# Main.net
KiCad netlist of a schematic drawn in Altium Designer
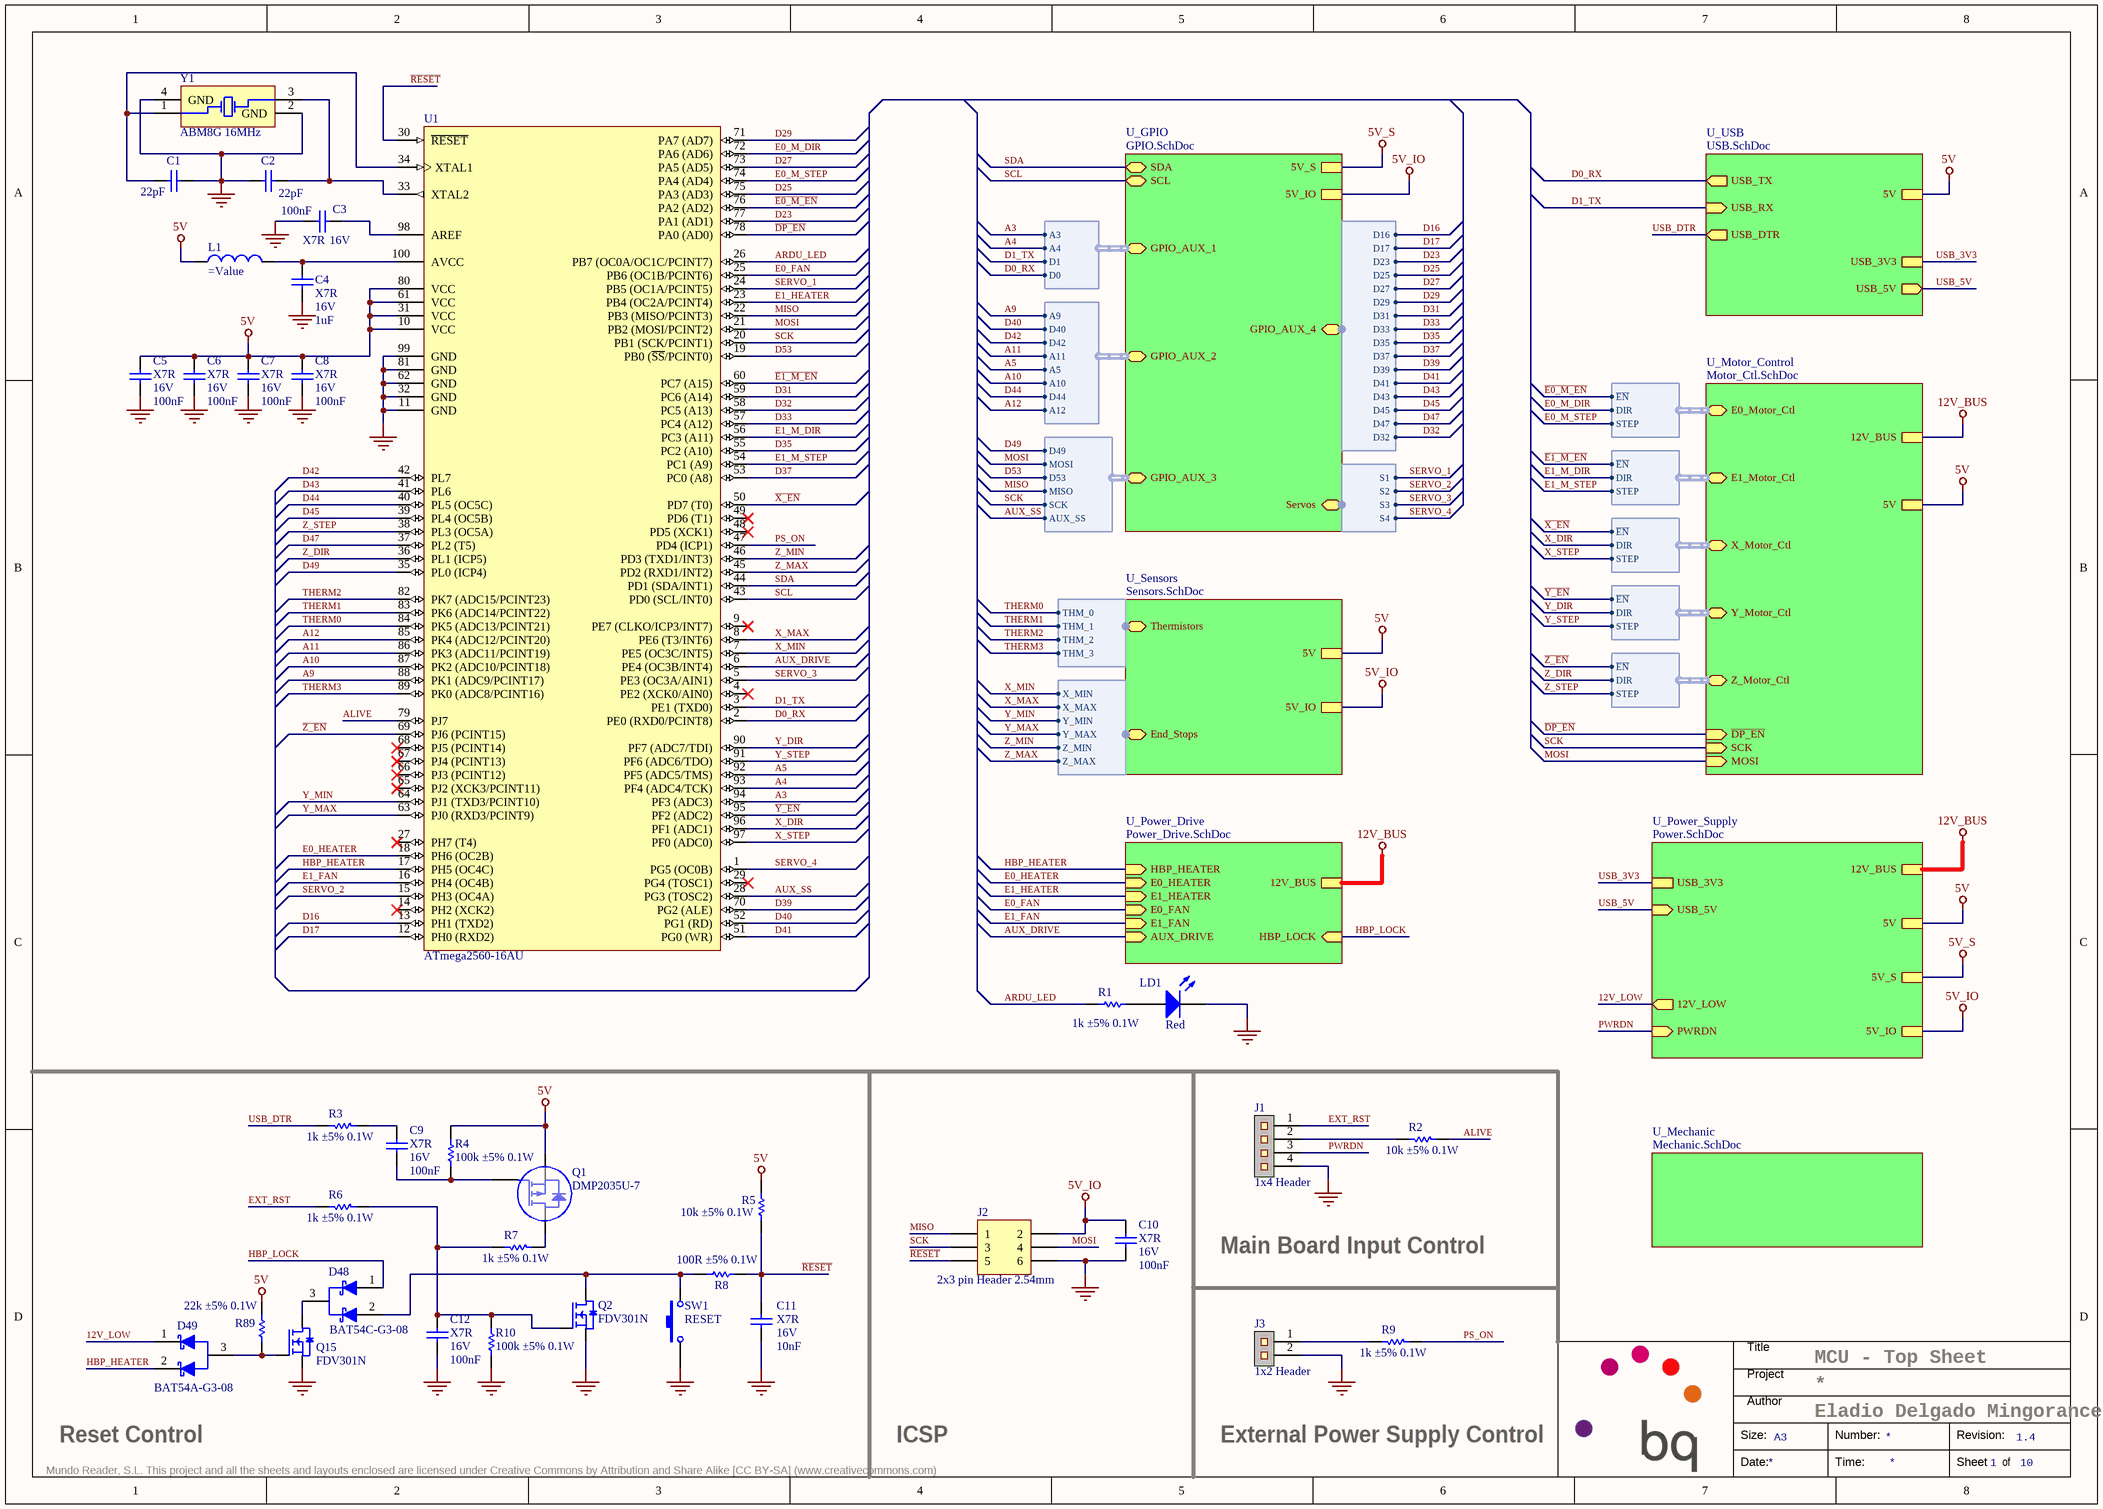
[diagram p0: Main.SchDoc]

(export (version "E")
  (design (tool "Eeschema 10.0.6"))
  (components
    (comp (ref "C1")
      (value "Capacitor")
      (footprint "C0603")
      (fields
        (field (name "VOLTAGE") "16V")
        (field (name "CAPACITANCE") "22pF")
        (field (name "PART NUMBER") "C0603_22pF_16V_±10%")
        (field (name "TOLERANCE") "±10%")
      )
      (libsource (lib "Pasives_Capacitor_SMD") (part "Capacitor"))
    )
    (comp (ref "C2")
      (value "Capacitor")
      (footprint "C0603")
      (fields
        (field (name "VOLTAGE") "16V")
        (field (name "CAPACITANCE") "22pF")
        (field (name "PART NUMBER") "C0603_22pF_16V_±10%")
        (field (name "TOLERANCE") "±10%")
      )
      (libsource (lib "Pasives_Capacitor_SMD") (part "Capacitor"))
    )
    (comp (ref "C3")
      (value "Capacitor")
      (footprint "C0603")
      (fields
        (field (name "DIELECTRIC") "X7R")
        (field (name "VOLTAGE") "16V")
        (field (name "CAPACITANCE") "100nF")
        (field (name "PART NUMBER") "C0603_100nF_16V_±10%")
        (field (name "TOLERANCE") "±10%")
        (field (name "MANUFACTURER") "Kemet")
      )
      (libsource (lib "Pasives_Capacitor_SMD") (part "Capacitor"))
    )
    (comp (ref "C4")
      (value "Capacitor")
      (footprint "C0603")
      (description "Capacitor SMD")
      (fields
        (field (name "DIELECTRIC") "X7R")
        (field (name "VOLTAGE") "16V")
        (field (name "CAPACITANCE") "1uF")
        (field (name "PART NUMBER") "C0603_1uF_16V_±10%_X7R")
        (field (name "TOLERANCE") "±10%")
      )
      (libsource (lib "Pasives_Capacitor_SMD") (part "Capacitor"))
    )
    (comp (ref "C5")
      (value "Capacitor")
      (footprint "C0603")
      (fields
        (field (name "DIELECTRIC") "X7R")
        (field (name "VOLTAGE") "16V")
        (field (name "CAPACITANCE") "100nF")
        (field (name "PART NUMBER") "C0603_100nF_16V_±10%")
        (field (name "TOLERANCE") "±10%")
        (field (name "MANUFACTURER") "Kemet")
      )
      (libsource (lib "Pasives_Capacitor_SMD") (part "Capacitor"))
    )
    (comp (ref "C6")
      (value "Capacitor")
      (footprint "C0603")
      (fields
        (field (name "DIELECTRIC") "X7R")
        (field (name "VOLTAGE") "16V")
        (field (name "CAPACITANCE") "100nF")
        (field (name "PART NUMBER") "C0603_100nF_16V_±10%")
        (field (name "TOLERANCE") "±10%")
        (field (name "MANUFACTURER") "Kemet")
      )
      (libsource (lib "Pasives_Capacitor_SMD") (part "Capacitor"))
    )
    (comp (ref "C7")
      (value "Capacitor")
      (footprint "C0603")
      (fields
        (field (name "DIELECTRIC") "X7R")
        (field (name "VOLTAGE") "16V")
        (field (name "CAPACITANCE") "100nF")
        (field (name "PART NUMBER") "C0603_100nF_16V_±10%")
        (field (name "TOLERANCE") "±10%")
        (field (name "MANUFACTURER") "Kemet")
      )
      (libsource (lib "Pasives_Capacitor_SMD") (part "Capacitor"))
    )
    (comp (ref "C8")
      (value "Capacitor")
      (footprint "C0603")
      (fields
        (field (name "DIELECTRIC") "X7R")
        (field (name "VOLTAGE") "16V")
        (field (name "CAPACITANCE") "100nF")
        (field (name "PART NUMBER") "C0603_100nF_16V_±10%")
        (field (name "TOLERANCE") "±10%")
        (field (name "MANUFACTURER") "Kemet")
      )
      (libsource (lib "Pasives_Capacitor_SMD") (part "Capacitor"))
    )
    (comp (ref "C9")
      (value "Capacitor")
      (footprint "C0603")
      (fields
        (field (name "DIELECTRIC") "X7R")
        (field (name "VOLTAGE") "16V")
        (field (name "CAPACITANCE") "100nF")
        (field (name "PART NUMBER") "C0603_100nF_16V_±10%")
        (field (name "TOLERANCE") "±10%")
        (field (name "MANUFACTURER") "Kemet")
      )
      (libsource (lib "Pasives_Capacitor_SMD") (part "Capacitor"))
    )
    (comp (ref "C10")
      (value "Capacitor")
      (footprint "C0603")
      (fields
        (field (name "DIELECTRIC") "X7R")
        (field (name "VOLTAGE") "16V")
        (field (name "CAPACITANCE") "100nF")
        (field (name "PART NUMBER") "C0603_100nF_16V_±10%")
        (field (name "TOLERANCE") "±10%")
        (field (name "MANUFACTURER") "Kemet")
      )
      (libsource (lib "Pasives_Capacitor_SMD") (part "Capacitor"))
    )
    (comp (ref "C11")
      (value "Capacitor")
      (footprint "C0603")
      (description "Capacitor SMD")
      (fields
        (field (name "DIELECTRIC") "X7R")
        (field (name "VOLTAGE") "16V")
        (field (name "CAPACITANCE") "10nF")
        (field (name "PART NUMBER") "C0603_10nF_16V_±10%")
        (field (name "TOLERANCE") "±10%")
      )
      (libsource (lib "Pasives_Capacitor_SMD") (part "Capacitor"))
    )
    (comp (ref "C12")
      (value "Capacitor")
      (footprint "C0603")
      (fields
        (field (name "DIELECTRIC") "X7R")
        (field (name "VOLTAGE") "16V")
        (field (name "CAPACITANCE") "100nF")
        (field (name "PART NUMBER") "C0603_100nF_16V_±10%")
        (field (name "TOLERANCE") "±10%")
        (field (name "MANUFACTURER") "Kemet")
      )
      (libsource (lib "Pasives_Capacitor_SMD") (part "Capacitor"))
    )
    (comp (ref "D48")
      (value "BAT54C-G3-08")
      (footprint "SOT23-3")
      (description "Dual Schottky Diode Common Cathode")
      (fields (field (name "PART NUMBER") "BAT54C") (field (name "MANUFACTURER") "Vishay"))
      (libsource (lib "Semiconductors_Diodes") (part "Dual_Diode_Schottky_BAT54C"))
    )
    (comp (ref "D49")
      (value "BAT54A-G3-08")
      (footprint "SOT23-3")
      (description "Dual Schottky Diode Common Anode")
      (fields (field (name "PART NUMBER") "BAT54A") (field (name "MANUFACTURER") "Vishay"))
      (libsource (lib "Semiconductors_Diodes") (part "Dual_Diode_Schottky_A"))
    )
    (comp (ref "J1")
      (value "1x4 Header")
      (footprint "1x4 MTE Straight Header 2.54mm")
      (description "1x4 MTE Straight Header 2.54mm")
      (fields
        (field (name "PART NUMBER") "CON_MTE_HDR_THT2.54_4")
        (field (name "MANUFACTURER") "TE Connectivity")
      )
      (libsource (lib "Conectores_MTE_Header_2.54") (part "1x4 MTE Straight Header 2.54mm"))
    )
    (comp (ref "J2")
      (value "2x3 pin Header 2.54mm")
      (footprint "2x3 Pin Header 2.54")
      (description "Connector, 6 pin Dual Header 2.54mm")
      (fields (field (name "MANUFACTURER") "Samtec") (field (name "PART NUMBER") "CON_DPH_THT2.54_6"))
      (libsource (lib "Conectores_PinHeader_2.54") (part "2x3 pin Header 2.54mm"))
    )
    (comp (ref "J3")
      (value "1x2 Header")
      (footprint "1x2 MTE Straight Header 2.54mm")
      (description "1x2 MTE Straight Header 2.54mm")
      (fields
        (field (name "PART NUMBER") "CON_MTE_HDR_THT2.54_2")
        (field (name "MANUFACTURER") "TE Connectivity")
      )
      (libsource (lib "Conectores_MTE_Header_2.54") (part "1x2 MTE Straight Header 2.54mm"))
    )
    (comp (ref "L1")
      (value "~")
      (footprint "L0805")
      (fields (field (name "PART NUMBER") "10uH_0,1A") (field (name "MANUFACTURER") "muRata"))
      (libsource (lib "Pasivos_Inductor_SMD") (part "Inductor"))
    )
    (comp (ref "LD1")
      (value "Red")
      (footprint "LED0603")
      (description "Light Emitting Diode")
      (fields (field (name "PART NUMBER") "HSMH-C190") (field (name "MANUFACTURER") "Avago Technologies"))
      (libsource (lib "Optoelectronics") (part "LED"))
    )
    (comp (ref "Q1")
      (value "DMP2035U-7")
      (footprint "SOT23-3")
      (description "Mosfet Channel P Enhancement Mode")
      (fields (field (name "PART NUMBER") "DMP2035U") (field (name "MANUFACTURER") "Diodes Incorporated"))
      (libsource (lib "Semiconductors_Transistors") (part "Mosfet_P"))
    )
    (comp (ref "Q2")
      (value "FDV301N")
      (footprint "SOT23-3")
      (description "Mosfet Channel N Enhancement Mode")
      (fields (field (name "MANUFACTURER") "Fairchild Semiconductor"))
      (libsource (lib "Semiconductors_Transistors") (part "Mosfet_N"))
    )
    (comp (ref "Q15")
      (value "FDV301N")
      (footprint "SOT23-3")
      (description "Mosfet Channel N Enhancement Mode")
      (fields (field (name "MANUFACTURER") "Fairchild Semiconductor"))
      (libsource (lib "Semiconductors_Transistors") (part "Mosfet_N"))
    )
    (comp (ref "R1")
      (value "1k ±5% 0.1W")
      (footprint "R0603")
      (description "Resistor")
      (fields (field (name "TOLERANCE") "±5%") (field (name "POWER") "0.1W"))
      (libsource (lib "Pasives_Resistor_SMD") (part "Resistor"))
    )
    (comp (ref "R2")
      (value "10k ±5% 0.1W")
      (footprint "R0603")
      (description "Resistor")
      (fields (field (name "TOLERANCE") "±5%") (field (name "POWER") "0.1W"))
      (libsource (lib "Pasives_Resistor_SMD") (part "Resistor"))
    )
    (comp (ref "R3")
      (value "1k ±5% 0.1W")
      (footprint "R0603")
      (description "Resistor")
      (fields (field (name "TOLERANCE") "±5%") (field (name "POWER") "0.1W"))
      (libsource (lib "Pasives_Resistor_SMD") (part "Resistor"))
    )
    (comp (ref "R4")
      (value "100k ±5% 0.1W")
      (footprint "R0603")
      (description "Resistor")
      (fields (field (name "TOLERANCE") "±5%") (field (name "POWER") "0.1W"))
      (libsource (lib "Pasives_Resistor_SMD") (part "Resistor"))
    )
    (comp (ref "R5")
      (value "10k ±5% 0.1W")
      (footprint "R0603")
      (description "Resistor")
      (fields (field (name "TOLERANCE") "±5%") (field (name "POWER") "0.1W"))
      (libsource (lib "Pasives_Resistor_SMD") (part "Resistor"))
    )
    (comp (ref "R6")
      (value "1k ±5% 0.1W")
      (footprint "R0603")
      (description "Resistor")
      (fields (field (name "TOLERANCE") "±5%") (field (name "POWER") "0.1W"))
      (libsource (lib "Pasives_Resistor_SMD") (part "Resistor"))
    )
    (comp (ref "R7")
      (value "1k ±5% 0.1W")
      (footprint "R0603")
      (description "Resistor")
      (fields (field (name "TOLERANCE") "±5%") (field (name "POWER") "0.1W"))
      (libsource (lib "Pasives_Resistor_SMD") (part "Resistor"))
    )
    (comp (ref "R8")
      (value "100R ±5% 0.1W")
      (footprint "R0603")
      (description "Resistor, SMD")
      (fields (field (name "TOLERANCE") "±5%") (field (name "POWER") "0.1W"))
      (libsource (lib "Pasives_Resistor_SMD") (part "Resistor"))
    )
    (comp (ref "R9")
      (value "1k ±5% 0.1W")
      (footprint "R0603")
      (description "Resistor")
      (fields (field (name "TOLERANCE") "±5%") (field (name "POWER") "0.1W"))
      (libsource (lib "Pasives_Resistor_SMD") (part "Resistor"))
    )
    (comp (ref "R10")
      (value "100k ±5% 0.1W")
      (footprint "R0603")
      (description "Resistor")
      (fields (field (name "TOLERANCE") "±5%") (field (name "POWER") "0.1W"))
      (libsource (lib "Pasives_Resistor_SMD") (part "Resistor"))
    )
    (comp (ref "R89")
      (value "22k ±5% 0.1W")
      (footprint "R0603")
      (description "Resistor, SMD")
      (fields (field (name "TOLERANCE") "±5%") (field (name "POWER") "0.1W"))
      (libsource (lib "Pasives_Resistor_SMD") (part "Resistor"))
    )
    (comp (ref "SW1")
      (value "RESET")
      (footprint "SW_Vert_THT_7.5x6x6.5")
      (description "Micro miniature pushbutton surface Switch")
      (fields (field (name "PART NUMBER") "SW Vertical THT") (field (name "MANUFACTURER") "C&K Components"))
      (libsource (lib "Electromechanical") (part "Switch"))
    )
    (comp (ref "U1")
      (value "ATmega2560-16AU")
      (footprint "TQFP100_05_MD")
      (fields (field (name "PART NUMBER") "Atmega2560") (field (name "MANUFACTURER") "Atmel"))
      (libsource (lib "Processor") (part "ATmega2560-16AU"))
    )
    (comp (ref "Y1")
      (value "ABM8G 16MHz")
      (footprint "ABM8G_3.2x2.5mm")
      (description "Crystal")
      (fields (field (name "TOLERANCE") "±20ppm") (field (name "MANUFACTURER") "Abracon"))
      (libsource (lib "Frequency") (part "Crystal 4 pin"))
    )
  )
  (nets
    (net (code "5") (name "/12V_LOW") (class "Default")
      (node (ref "D49") (pin "1") (pinfunction "A1_1") (pintype "passive"))
    )
    (net (code "6") (name "/A3") (class "Default")
      (node (ref "U1") (pin "94") (pinfunction "PF3_(ADC3)_94") (pintype "bidirectional"))
    )
    (net (code "7") (name "/A4") (class "Default")
      (node (ref "U1") (pin "93") (pinfunction "PF4_(ADC4/TCK)_93") (pintype "bidirectional"))
    )
    (net (code "8") (name "/A5") (class "Default")
      (node (ref "U1") (pin "92") (pinfunction "PF5_(ADC5/TMS)_92") (pintype "bidirectional"))
    )
    (net (code "9") (name "/A9") (class "Default")
      (node (ref "U1") (pin "88") (pinfunction "PK1_(ADC9/PCINT17)_88") (pintype "bidirectional"))
    )
    (net (code "10") (name "/A10") (class "Default")
      (node (ref "U1") (pin "87") (pinfunction "PK2_(ADC10/PCINT18)_87") (pintype "bidirectional"))
    )
    (net (code "11") (name "/A11") (class "Default")
      (node (ref "U1") (pin "86") (pinfunction "PK3_(ADC11/PCINT19)_86") (pintype "bidirectional"))
    )
    (net (code "12") (name "/A12") (class "Default")
      (node (ref "U1") (pin "85") (pinfunction "PK4_(ADC12/PCINT20)_85") (pintype "bidirectional"))
    )
    (net (code "13") (name "/ALIVE") (class "Default")
      (node (ref "R2") (pin "1") (pinfunction "1_1") (pintype "passive"))
      (node (ref "U1") (pin "79") (pinfunction "PJ7_79") (pintype "bidirectional"))
    )
    (net (code "14") (name "/ARDU_LED") (class "Default")
      (node (ref "R1") (pin "1") (pinfunction "1_1") (pintype "passive"))
      (node (ref "U1") (pin "26") (pinfunction "PB7_(OC0A/OC1C/PCINT7)_26") (pintype "bidirectional"))
    )
    (net (code "15") (name "/AUX_DRIVE") (class "Default")
      (node (ref "U1") (pin "6") (pinfunction "PE4_(OC3B/INT4)_6") (pintype "bidirectional"))
    )
    (net (code "16") (name "/AUX_SS") (class "Default")
      (node (ref "U1") (pin "28") (pinfunction "PG3_(TOSC2)_28") (pintype "bidirectional"))
    )
    (net (code "17") (name "/D0_RX") (class "Default")
      (node (ref "U1") (pin "2") (pinfunction "PE0_(RXD0/PCINT8)_2") (pintype "bidirectional"))
    )
    (net (code "18") (name "/D1_TX") (class "Default")
      (node (ref "U1") (pin "3") (pinfunction "PE1_(TXD0)_3") (pintype "bidirectional"))
    )
    (net (code "19") (name "/D16") (class "Default")
      (node (ref "U1") (pin "13") (pinfunction "PH1_(TXD2)_13") (pintype "bidirectional"))
    )
    (net (code "20") (name "/D17") (class "Default")
      (node (ref "U1") (pin "12") (pinfunction "PH0_(RXD2)_12") (pintype "bidirectional"))
    )
    (net (code "21") (name "/D23") (class "Default")
      (node (ref "U1") (pin "77") (pinfunction "PA1_(AD1)_77") (pintype "bidirectional"))
    )
    (net (code "22") (name "/D25") (class "Default")
      (node (ref "U1") (pin "75") (pinfunction "PA3_(AD3)_75") (pintype "bidirectional"))
    )
    (net (code "23") (name "/D27") (class "Default")
      (node (ref "U1") (pin "73") (pinfunction "PA5_(AD5)_73") (pintype "bidirectional"))
    )
    (net (code "24") (name "/D29") (class "Default")
      (node (ref "U1") (pin "71") (pinfunction "PA7_(AD7)_71") (pintype "bidirectional"))
    )
    (net (code "25") (name "/D31") (class "Default")
      (node (ref "U1") (pin "59") (pinfunction "PC6_(A14)_59") (pintype "bidirectional"))
    )
    (net (code "26") (name "/D32") (class "Default")
      (node (ref "U1") (pin "58") (pinfunction "PC5_(A13)_58") (pintype "bidirectional"))
    )
    (net (code "27") (name "/D33") (class "Default")
      (node (ref "U1") (pin "57") (pinfunction "PC4_(A12)_57") (pintype "bidirectional"))
    )
    (net (code "28") (name "/D35") (class "Default")
      (node (ref "U1") (pin "55") (pinfunction "PC2_(A10)_55") (pintype "bidirectional"))
    )
    (net (code "29") (name "/D37") (class "Default")
      (node (ref "U1") (pin "53") (pinfunction "PC0_(A8)_53") (pintype "bidirectional"))
    )
    (net (code "30") (name "/D39") (class "Default")
      (node (ref "U1") (pin "70") (pinfunction "PG2_(ALE)_70") (pintype "bidirectional"))
    )
    (net (code "31") (name "/D40") (class "Default")
      (node (ref "U1") (pin "52") (pinfunction "PG1_(RD)_52") (pintype "bidirectional"))
    )
    (net (code "32") (name "/D41") (class "Default")
      (node (ref "U1") (pin "51") (pinfunction "PG0_(WR)_51") (pintype "bidirectional"))
    )
    (net (code "33") (name "/D42") (class "Default")
      (node (ref "U1") (pin "42") (pinfunction "PL7_42") (pintype "bidirectional"))
    )
    (net (code "34") (name "/D43") (class "Default")
      (node (ref "U1") (pin "41") (pinfunction "PL6_41") (pintype "bidirectional"))
    )
    (net (code "35") (name "/D44") (class "Default")
      (node (ref "U1") (pin "40") (pinfunction "PL5_(OC5C)_40") (pintype "bidirectional"))
    )
    (net (code "36") (name "/D45") (class "Default")
      (node (ref "U1") (pin "39") (pinfunction "PL4_(OC5B)_39") (pintype "bidirectional"))
    )
    (net (code "37") (name "/D47") (class "Default")
      (node (ref "U1") (pin "37") (pinfunction "PL2_(T5)_37") (pintype "bidirectional"))
    )
    (net (code "38") (name "/D49") (class "Default")
      (node (ref "U1") (pin "35") (pinfunction "PL0_(ICP4)_35") (pintype "bidirectional"))
    )
    (net (code "39") (name "/D53") (class "Default")
      (node (ref "U1") (pin "19") (pinfunction "PB0_(~{SS}/PCINT0)_19") (pintype "bidirectional"))
    )
    (net (code "40") (name "/DP_EN") (class "Default")
      (node (ref "U1") (pin "78") (pinfunction "PA0_(AD0)_78") (pintype "bidirectional"))
    )
    (net (code "41") (name "/E0_FAN") (class "Default")
      (node (ref "U1") (pin "25") (pinfunction "PB6_(OC1B/PCINT6)_25") (pintype "bidirectional"))
    )
    (net (code "42") (name "/E0_HEATER") (class "Default")
      (node (ref "U1") (pin "18") (pinfunction "PH6_(OC2B)_18") (pintype "bidirectional"))
    )
    (net (code "43") (name "/E0_M_DIR") (class "Default")
      (node (ref "U1") (pin "72") (pinfunction "PA6_(AD6)_72") (pintype "bidirectional"))
    )
    (net (code "44") (name "/E0_M_EN") (class "Default")
      (node (ref "U1") (pin "76") (pinfunction "PA2_(AD2)_76") (pintype "bidirectional"))
    )
    (net (code "45") (name "/E0_M_STEP") (class "Default")
      (node (ref "U1") (pin "74") (pinfunction "PA4_(AD4)_74") (pintype "bidirectional"))
    )
    (net (code "46") (name "/E1_FAN") (class "Default")
      (node (ref "U1") (pin "16") (pinfunction "PH4_(OC4B)_16") (pintype "bidirectional"))
    )
    (net (code "47") (name "/E1_HEATER") (class "Default")
      (node (ref "U1") (pin "23") (pinfunction "PB4_(OC2A/PCINT4)_23") (pintype "bidirectional"))
    )
    (net (code "48") (name "/E1_M_DIR") (class "Default")
      (node (ref "U1") (pin "56") (pinfunction "PC3_(A11)_56") (pintype "bidirectional"))
    )
    (net (code "49") (name "/E1_M_EN") (class "Default")
      (node (ref "U1") (pin "60") (pinfunction "PC7_(A15)_60") (pintype "bidirectional"))
    )
    (net (code "50") (name "/E1_M_STEP") (class "Default")
      (node (ref "U1") (pin "54") (pinfunction "PC1_(A9)_54") (pintype "bidirectional"))
    )
    (net (code "51") (name "/EXT_RST") (class "Default")
      (node (ref "J1") (pin "1") (pinfunction "1_1") (pintype "passive"))
      (node (ref "R6") (pin "2") (pinfunction "2_2") (pintype "passive"))
    )
    (net (code "54") (name "/HBP_HEATER") (class "Default")
      (node (ref "D49") (pin "2") (pinfunction "A2_2") (pintype "passive"))
      (node (ref "U1") (pin "17") (pinfunction "PH5_(OC4C)_17") (pintype "bidirectional"))
    )
    (net (code "55") (name "/HBP_LOCK") (class "Default")
      (node (ref "D48") (pin "1") (pinfunction "A1_1") (pintype "passive"))
    )
    (net (code "56") (name "/MISO") (class "Default")
      (node (ref "J2") (pin "1") (pinfunction "1_1") (pintype "passive"))
      (node (ref "U1") (pin "22") (pinfunction "PB3_(MISO/PCINT3)_22") (pintype "bidirectional"))
    )
    (net (code "57") (name "/MOSI") (class "Default")
      (node (ref "J2") (pin "4") (pinfunction "4_4") (pintype "passive"))
      (node (ref "U1") (pin "21") (pinfunction "PB2_(MOSI/PCINT2)_21") (pintype "bidirectional"))
    )
    (net (code "58") (name "/PS_ON") (class "Default")
      (node (ref "R9") (pin "1") (pinfunction "1_1") (pintype "passive"))
      (node (ref "U1") (pin "47") (pinfunction "PD4_(ICP1)_47") (pintype "bidirectional"))
    )
    (net (code "59") (name "/PWRDN") (class "Default")
      (node (ref "J1") (pin "3") (pinfunction "3_3") (pintype "passive"))
    )
    (net (code "60") (name "/RESET") (class "Default")
      (node (ref "C11") (pin "2") (pinfunction "2_2") (pintype "passive"))
      (node (ref "J2") (pin "5") (pinfunction "5_5") (pintype "passive"))
      (node (ref "R5") (pin "1") (pinfunction "1_1") (pintype "passive"))
      (node (ref "R8") (pin "2") (pinfunction "2_2") (pintype "passive"))
      (node (ref "U1") (pin "30") (pinfunction "~{RESET}_30") (pintype "input"))
    )
    (net (code "61") (name "/SCK") (class "Default")
      (node (ref "J2") (pin "3") (pinfunction "3_3") (pintype "passive"))
      (node (ref "U1") (pin "20") (pinfunction "PB1_(SCK/PCINT1)_20") (pintype "bidirectional"))
    )
    (net (code "62") (name "/SCL") (class "Default")
      (node (ref "U1") (pin "43") (pinfunction "PD0_(SCL/INT0)_43") (pintype "bidirectional"))
    )
    (net (code "63") (name "/SDA") (class "Default")
      (node (ref "U1") (pin "44") (pinfunction "PD1_(SDA/INT1)_44") (pintype "bidirectional"))
    )
    (net (code "64") (name "/SERVO_1") (class "Default")
      (node (ref "U1") (pin "24") (pinfunction "PB5_(OC1A/PCINT5)_24") (pintype "bidirectional"))
    )
    (net (code "65") (name "/SERVO_2") (class "Default")
      (node (ref "U1") (pin "15") (pinfunction "PH3_(OC4A)_15") (pintype "bidirectional"))
    )
    (net (code "66") (name "/SERVO_3") (class "Default")
      (node (ref "U1") (pin "5") (pinfunction "PE3_(OC3A/AIN1)_5") (pintype "bidirectional"))
    )
    (net (code "67") (name "/SERVO_4") (class "Default")
      (node (ref "U1") (pin "1") (pinfunction "PG5_(OC0B)_1") (pintype "bidirectional"))
    )
    (net (code "69") (name "/THERM0") (class "Default")
      (node (ref "U1") (pin "84") (pinfunction "PK5_(ADC13/PCINT21)_84") (pintype "bidirectional"))
    )
    (net (code "70") (name "/THERM1") (class "Default")
      (node (ref "U1") (pin "83") (pinfunction "PK6_(ADC14/PCINT22)_83") (pintype "bidirectional"))
    )
    (net (code "71") (name "/THERM2") (class "Default")
      (node (ref "U1") (pin "82") (pinfunction "PK7_(ADC15/PCINT23)_82") (pintype "bidirectional"))
    )
    (net (code "72") (name "/THERM3") (class "Default")
      (node (ref "U1") (pin "89") (pinfunction "PK0_(ADC8/PCINT16)_89") (pintype "bidirectional"))
    )
    (net (code "76") (name "/USB_DTR") (class "Default")
      (node (ref "R3") (pin "2") (pinfunction "2_2") (pintype "passive"))
    )
    (net (code "77") (name "/X_DIR") (class "Default")
      (node (ref "U1") (pin "96") (pinfunction "PF1_(ADC1)_96") (pintype "bidirectional"))
    )
    (net (code "78") (name "/X_EN") (class "Default")
      (node (ref "U1") (pin "50") (pinfunction "PD7_(T0)_50") (pintype "bidirectional"))
    )
    (net (code "79") (name "/X_MAX") (class "Default")
      (node (ref "U1") (pin "8") (pinfunction "PE6_(T3/INT6)_8") (pintype "bidirectional"))
    )
    (net (code "80") (name "/X_MIN") (class "Default")
      (node (ref "U1") (pin "7") (pinfunction "PE5_(OC3C/INT5)_7") (pintype "bidirectional"))
    )
    (net (code "81") (name "/X_STEP") (class "Default")
      (node (ref "U1") (pin "97") (pinfunction "PF0_(ADC0)_97") (pintype "bidirectional"))
    )
    (net (code "82") (name "/Y_DIR") (class "Default")
      (node (ref "U1") (pin "90") (pinfunction "PF7_(ADC7/TDI)_90") (pintype "bidirectional"))
    )
    (net (code "83") (name "/Y_EN") (class "Default")
      (node (ref "U1") (pin "95") (pinfunction "PF2_(ADC2)_95") (pintype "bidirectional"))
    )
    (net (code "84") (name "/Y_MAX") (class "Default")
      (node (ref "U1") (pin "63") (pinfunction "PJ0_(RXD3/PCINT9)_63") (pintype "bidirectional"))
    )
    (net (code "85") (name "/Y_MIN") (class "Default")
      (node (ref "U1") (pin "64") (pinfunction "PJ1_(TXD3/PCINT10)_64") (pintype "bidirectional"))
    )
    (net (code "86") (name "/Y_STEP") (class "Default")
      (node (ref "U1") (pin "91") (pinfunction "PF6_(ADC6/TDO)_91") (pintype "bidirectional"))
    )
    (net (code "87") (name "/Z_DIR") (class "Default")
      (node (ref "U1") (pin "36") (pinfunction "PL1_(ICP5)_36") (pintype "bidirectional"))
    )
    (net (code "88") (name "/Z_EN") (class "Default")
      (node (ref "U1") (pin "69") (pinfunction "PJ6_(PCINT15)_69") (pintype "bidirectional"))
    )
    (net (code "89") (name "/Z_MAX") (class "Default")
      (node (ref "U1") (pin "45") (pinfunction "PD2_(RXD1/INT2)_45") (pintype "bidirectional"))
    )
    (net (code "90") (name "/Z_MIN") (class "Default")
      (node (ref "U1") (pin "46") (pinfunction "PD3_(TXD1/INT3)_46") (pintype "bidirectional"))
    )
    (net (code "91") (name "/Z_STEP") (class "Default")
      (node (ref "U1") (pin "38") (pinfunction "PL3_(OC5A)_38") (pintype "bidirectional"))
    )
    (net (code "96") (name "5V") (class "Default")
      (node (ref "C5") (pin "2") (pinfunction "2_2") (pintype "passive"))
      (node (ref "C6") (pin "2") (pinfunction "2_2") (pintype "passive"))
      (node (ref "C7") (pin "2") (pinfunction "2_2") (pintype "passive"))
      (node (ref "C8") (pin "2") (pinfunction "2_2") (pintype "passive"))
      (node (ref "L1") (pin "1") (pinfunction "1_1") (pintype "passive"))
      (node (ref "Q1") (pin "2") (pinfunction "S_2") (pintype "passive"))
      (node (ref "R4") (pin "2") (pinfunction "2_2") (pintype "passive"))
      (node (ref "R5") (pin "2") (pinfunction "2_2") (pintype "passive"))
      (node (ref "R89") (pin "2") (pinfunction "2_2") (pintype "passive"))
      (node (ref "U1") (pin "10") (pinfunction "VCC_10") (pintype "power_in"))
      (node (ref "U1") (pin "31") (pinfunction "VCC_31") (pintype "power_in"))
      (node (ref "U1") (pin "61") (pinfunction "VCC_61") (pintype "power_in"))
      (node (ref "U1") (pin "80") (pinfunction "VCC_80") (pintype "power_in"))
    )
    (net (code "97") (name "5V_IO") (class "Default")
      (node (ref "C10") (pin "2") (pinfunction "2_2") (pintype "passive"))
      (node (ref "J2") (pin "2") (pinfunction "2_2") (pintype "passive"))
    )
    (net (code "100") (name "GND") (class "Default")
      (node (ref "C1") (pin "1") (pinfunction "1_1") (pintype "passive"))
      (node (ref "C10") (pin "1") (pinfunction "1_1") (pintype "passive"))
      (node (ref "C11") (pin "1") (pinfunction "1_1") (pintype "passive"))
      (node (ref "C12") (pin "1") (pinfunction "1_1") (pintype "passive"))
      (node (ref "C2") (pin "1") (pinfunction "1_1") (pintype "passive"))
      (node (ref "C3") (pin "2") (pinfunction "2_2") (pintype "passive"))
      (node (ref "C4") (pin "1") (pinfunction "1_1") (pintype "passive"))
      (node (ref "C5") (pin "1") (pinfunction "1_1") (pintype "passive"))
      (node (ref "C6") (pin "1") (pinfunction "1_1") (pintype "passive"))
      (node (ref "C7") (pin "1") (pinfunction "1_1") (pintype "passive"))
      (node (ref "C8") (pin "1") (pinfunction "1_1") (pintype "passive"))
      (node (ref "J1") (pin "4") (pinfunction "4_4") (pintype "passive"))
      (node (ref "J2") (pin "6") (pinfunction "6_6") (pintype "passive"))
      (node (ref "J3") (pin "2") (pinfunction "2_2") (pintype "passive"))
      (node (ref "LD1") (pin "K") (pinfunction "K_K") (pintype "passive"))
      (node (ref "Q15") (pin "2") (pinfunction "S_2") (pintype "passive"))
      (node (ref "Q2") (pin "2") (pinfunction "S_2") (pintype "passive"))
      (node (ref "R10") (pin "1") (pinfunction "1_1") (pintype "passive"))
      (node (ref "SW1") (pin "1") (pinfunction "1_1") (pintype "passive"))
      (node (ref "U1") (pin "11") (pinfunction "GND_11") (pintype "power_in"))
      (node (ref "U1") (pin "32") (pinfunction "GND_32") (pintype "power_in"))
      (node (ref "U1") (pin "62") (pinfunction "GND_62") (pintype "power_in"))
      (node (ref "U1") (pin "81") (pinfunction "GND_81") (pintype "power_in"))
      (node (ref "U1") (pin "99") (pinfunction "GND_99") (pintype "power_in"))
      (node (ref "Y1") (pin "2") (pinfunction "GND_2") (pintype "passive"))
      (node (ref "Y1") (pin "4") (pinfunction "GND_4") (pintype "passive"))
    )
    (net (code "101") (name "Net-(C9-Pad2)") (class "Default")
      (node (ref "C9") (pin "2") (pinfunction "2_2") (pintype "passive"))
      (node (ref "R3") (pin "1") (pinfunction "1_1") (pintype "passive"))
    )
    (net (code "102") (name "Net-(D48-A2)") (class "Default")
      (node (ref "D48") (pin "2") (pinfunction "A2_2") (pintype "passive"))
      (node (ref "Q2") (pin "3") (pinfunction "D_3") (pintype "passive"))
      (node (ref "R8") (pin "1") (pinfunction "1_1") (pintype "passive"))
      (node (ref "SW1") (pin "2") (pinfunction "2_2") (pintype "passive"))
    )
    (net (code "103") (name "Net-(D48-K)") (class "Default")
      (node (ref "D48") (pin "3") (pinfunction "K_3") (pintype "passive"))
      (node (ref "Q15") (pin "3") (pinfunction "D_3") (pintype "passive"))
    )
    (net (code "104") (name "Net-(D49-K)") (class "Default")
      (node (ref "D49") (pin "3") (pinfunction "K_3") (pintype "passive"))
      (node (ref "Q15") (pin "1") (pinfunction "G_1") (pintype "passive"))
      (node (ref "R89") (pin "1") (pinfunction "1_1") (pintype "passive"))
    )
    (net (code "105") (name "Net-(J1-Pad2)") (class "Default")
      (node (ref "J1") (pin "2") (pinfunction "2_2") (pintype "passive"))
      (node (ref "R2") (pin "2") (pinfunction "2_2") (pintype "passive"))
    )
    (net (code "106") (name "Net-(J3-Pad1)") (class "Default")
      (node (ref "J3") (pin "1") (pinfunction "1_1") (pintype "passive"))
      (node (ref "R9") (pin "2") (pinfunction "2_2") (pintype "passive"))
    )
    (net (code "107") (name "Net-(LD1-PadA)") (class "Default")
      (node (ref "LD1") (pin "A") (pinfunction "A_A") (pintype "passive"))
      (node (ref "R1") (pin "2") (pinfunction "2_2") (pintype "passive"))
    )
    (net (code "108") (name "Net-(Q1-D)") (class "Default")
      (node (ref "Q1") (pin "3") (pinfunction "D_3") (pintype "passive"))
      (node (ref "R7") (pin "1") (pinfunction "1_1") (pintype "passive"))
    )
    (net (code "109") (name "Net-(Q1-G)") (class "Default")
      (node (ref "C9") (pin "1") (pinfunction "1_1") (pintype "passive"))
      (node (ref "Q1") (pin "1") (pinfunction "G_1") (pintype "passive"))
      (node (ref "R4") (pin "1") (pinfunction "1_1") (pintype "passive"))
    )
    (net (code "110") (name "Net-(Q2-G)") (class "Default")
      (node (ref "C12") (pin "2") (pinfunction "2_2") (pintype "passive"))
      (node (ref "Q2") (pin "1") (pinfunction "G_1") (pintype "passive"))
      (node (ref "R10") (pin "2") (pinfunction "2_2") (pintype "passive"))
      (node (ref "R6") (pin "1") (pinfunction "1_1") (pintype "passive"))
      (node (ref "R7") (pin "2") (pinfunction "2_2") (pintype "passive"))
    )
    (net (code "111") (name "Net-(U1-AREF)") (class "Default")
      (node (ref "C3") (pin "1") (pinfunction "1_1") (pintype "passive"))
      (node (ref "U1") (pin "98") (pinfunction "AREF_98") (pintype "power_in"))
    )
    (net (code "112") (name "Net-(U1-AVCC)") (class "Default")
      (node (ref "C4") (pin "2") (pinfunction "2_2") (pintype "passive"))
      (node (ref "L1") (pin "2") (pinfunction "2_2") (pintype "passive"))
      (node (ref "U1") (pin "100") (pinfunction "AVCC_100") (pintype "power_in"))
    )
    (net (code "113") (name "Net-(U1-XTAL1)") (class "Default")
      (node (ref "C1") (pin "2") (pinfunction "2_2") (pintype "passive"))
      (node (ref "U1") (pin "34") (pinfunction "XTAL1_34") (pintype "input"))
      (node (ref "Y1") (pin "1") (pinfunction "OSC1_1") (pintype "passive"))
    )
    (net (code "114") (name "Net-(U1-XTAL2)") (class "Default")
      (node (ref "C2") (pin "2") (pinfunction "2_2") (pintype "passive"))
      (node (ref "U1") (pin "33") (pinfunction "XTAL2_33") (pintype "output"))
      (node (ref "Y1") (pin "3") (pinfunction "OSC2_3") (pintype "passive"))
    )
    (net (code "115") (name "unconnected-(U1-PD5_(XCK1)-Pad48)") (class "Default")
      (node (ref "U1") (pin "48") (pinfunction "PD5_(XCK1)_48") (pintype "bidirectional+no_connect"))
    )
    (net (code "116") (name "unconnected-(U1-PD6_(T1)-Pad49)") (class "Default")
      (node (ref "U1") (pin "49") (pinfunction "PD6_(T1)_49") (pintype "bidirectional+no_connect"))
    )
    (net (code "117") (name "unconnected-(U1-PE2_(XCK0{slash}AIN0)-Pad4)") (class "Default")
      (node (ref "U1") (pin "4") (pinfunction "PE2_(XCK0/AIN0)_4") (pintype "bidirectional+no_connect"))
    )
    (net (code "118") (name "unconnected-(U1-PE7_(CLKO{slash}ICP3{slash}INT7)-Pad9)") (class "Default")
      (node (ref "U1") (pin "9") (pinfunction "PE7_(CLKO/ICP3/INT7)_9") (pintype "bidirectional+no_connect"))
    )
    (net (code "119") (name "unconnected-(U1-PG4_(TOSC1)-Pad29)") (class "Default")
      (node (ref "U1") (pin "29") (pinfunction "PG4_(TOSC1)_29") (pintype "bidirectional+no_connect"))
    )
    (net (code "120") (name "unconnected-(U1-PH2_(XCK2)-Pad14)") (class "Default")
      (node (ref "U1") (pin "14") (pinfunction "PH2_(XCK2)_14") (pintype "bidirectional+no_connect"))
    )
    (net (code "121") (name "unconnected-(U1-PH7_(T4)-Pad27)") (class "Default")
      (node (ref "U1") (pin "27") (pinfunction "PH7_(T4)_27") (pintype "bidirectional+no_connect"))
    )
    (net (code "122") (name "unconnected-(U1-PJ2_(XCK3{slash}PCINT11)-Pad65)") (class "Default")
      (node (ref "U1") (pin "65") (pinfunction "PJ2_(XCK3/PCINT11)_65") (pintype "bidirectional+no_connect"))
    )
    (net (code "123") (name "unconnected-(U1-PJ3_(PCINT12)-Pad66)") (class "Default")
      (node (ref "U1") (pin "66") (pinfunction "PJ3_(PCINT12)_66") (pintype "bidirectional+no_connect"))
    )
    (net (code "124") (name "unconnected-(U1-PJ4_(PCINT13)-Pad67)") (class "Default")
      (node (ref "U1") (pin "67") (pinfunction "PJ4_(PCINT13)_67") (pintype "bidirectional+no_connect"))
    )
    (net (code "125") (name "unconnected-(U1-PJ5_(PCINT14)-Pad68)") (class "Default")
      (node (ref "U1") (pin "68") (pinfunction "PJ5_(PCINT14)_68") (pintype "bidirectional+no_connect"))
    )
  )
)
